# amp_summator_v_1_0.net
KiCad netlist of a schematic drawn in EAGLE
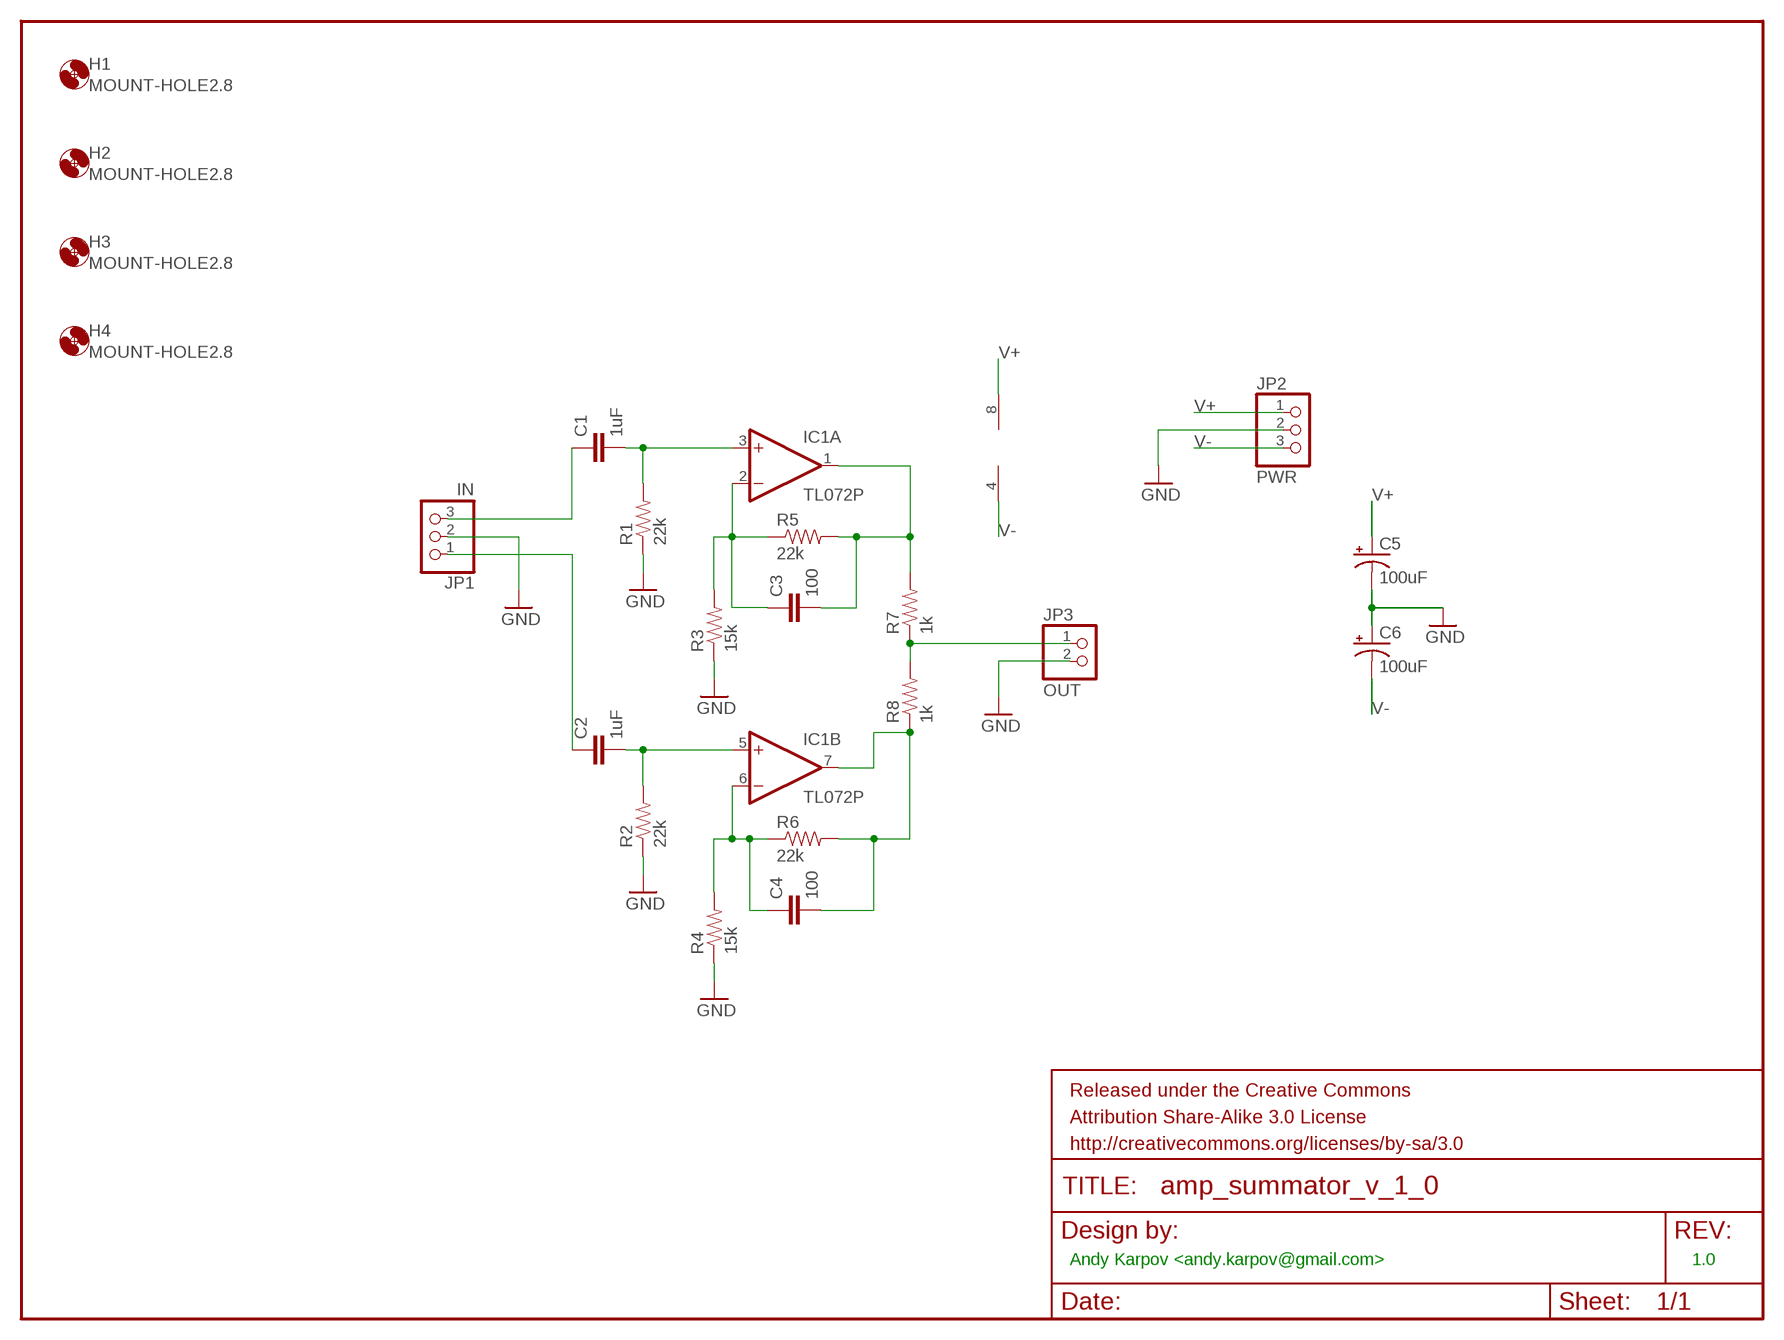
[diagram p0: schematic, sheet 1]

(export (version "E")
  (design (tool "Eeschema 10.0.6"))
  (components
    (comp (ref "C1")
      (value "1uF")
      (footprint "eagle-import:CAP-PTH-5MM")
      (libsource (lib "eagle-import") (part "CAPPTH1"))
    )
    (comp (ref "C2")
      (value "1uF")
      (footprint "eagle-import:CAP-PTH-5MM")
      (libsource (lib "eagle-import") (part "CAPPTH1"))
    )
    (comp (ref "C3")
      (value "100")
      (footprint "eagle-import:CAP-PTH-5MM")
      (libsource (lib "eagle-import") (part "CAPPTH1"))
    )
    (comp (ref "C4")
      (value "100")
      (footprint "eagle-import:CAP-PTH-5MM")
      (libsource (lib "eagle-import") (part "CAPPTH1"))
    )
    (comp (ref "C5")
      (value "100uF")
      (footprint "eagle-import:CPOL-RADIAL-100UF-25V")
      (libsource (lib "eagle-import") (part "CAP_POLPTH1"))
    )
    (comp (ref "C6")
      (value "100uF")
      (footprint "eagle-import:CPOL-RADIAL-100UF-25V")
      (libsource (lib "eagle-import") (part "CAP_POLPTH1"))
    )
    (comp (ref "FRAME1")
      (value "FRAME-LETTER")
      (footprint "eagle-import:CREATIVE_COMMONS")
      (libsource (lib "eagle-import") (part "FRAME-LETTER"))
    )
    (comp (ref "H1")
      (value "MOUNT-HOLE2.8")
      (footprint "eagle-import:2,8")
      (libsource (lib "eagle-import") (part "MOUNT-HOLE2.8"))
    )
    (comp (ref "H2")
      (value "MOUNT-HOLE2.8")
      (footprint "eagle-import:2,8")
      (libsource (lib "eagle-import") (part "MOUNT-HOLE2.8"))
    )
    (comp (ref "H3")
      (value "MOUNT-HOLE2.8")
      (footprint "eagle-import:2,8")
      (libsource (lib "eagle-import") (part "MOUNT-HOLE2.8"))
    )
    (comp (ref "H4")
      (value "MOUNT-HOLE2.8")
      (footprint "eagle-import:2,8")
      (libsource (lib "eagle-import") (part "MOUNT-HOLE2.8"))
    )
    (comp (ref "IC1")
      (value "TL072P")
      (footprint "eagle-import:DIL08")
      (libsource (lib "eagle-import") (part "TL072P"))
    )
    (comp (ref "JP1")
      (value "IN")
      (footprint "eagle-import:1X03")
      (libsource (lib "eagle-import") (part "PINHD-1X3"))
    )
    (comp (ref "JP2")
      (value "PWR")
      (footprint "eagle-import:1X03")
      (libsource (lib "eagle-import") (part "PINHD-1X3"))
    )
    (comp (ref "JP3")
      (value "OUT")
      (footprint "eagle-import:1X02")
      (libsource (lib "eagle-import") (part "PINHD-1X2"))
    )
    (comp (ref "R1")
      (value "22k")
      (footprint "eagle-import:AXIAL-0.4")
      (libsource (lib "eagle-import") (part "RESISTORPTH-1/4W"))
    )
    (comp (ref "R2")
      (value "22k")
      (footprint "eagle-import:AXIAL-0.4")
      (libsource (lib "eagle-import") (part "RESISTORPTH-1/4W"))
    )
    (comp (ref "R3")
      (value "15k")
      (footprint "eagle-import:AXIAL-0.4")
      (libsource (lib "eagle-import") (part "RESISTORPTH-1/4W"))
    )
    (comp (ref "R4")
      (value "15k")
      (footprint "eagle-import:AXIAL-0.4")
      (libsource (lib "eagle-import") (part "RESISTORPTH-1/4W"))
    )
    (comp (ref "R5")
      (value "22k")
      (footprint "eagle-import:AXIAL-0.4")
      (libsource (lib "eagle-import") (part "RESISTORPTH-1/4W"))
    )
    (comp (ref "R6")
      (value "22k")
      (footprint "eagle-import:AXIAL-0.4")
      (libsource (lib "eagle-import") (part "RESISTORPTH-1/4W"))
    )
    (comp (ref "R7")
      (value "1k")
      (footprint "eagle-import:AXIAL-0.4")
      (libsource (lib "eagle-import") (part "RESISTORPTH-1/4W"))
    )
    (comp (ref "R8")
      (value "1k")
      (footprint "eagle-import:AXIAL-0.4")
      (libsource (lib "eagle-import") (part "RESISTORPTH-1/4W"))
    )
  )
  (nets
    (net (code "1") (name "/V+") (class "Default")
      (node (ref "C5") (pin "1") (pinfunction "+_1") (pintype "passive"))
      (node (ref "IC1") (pin "8") (pinfunction "V+_8") (pintype "power_in"))
      (node (ref "JP2") (pin "1") (pinfunction "1_1") (pintype "passive"))
    )
    (net (code "2") (name "/V-") (class "Default")
      (node (ref "C6") (pin "2") (pinfunction "-_2") (pintype "passive"))
      (node (ref "IC1") (pin "4") (pinfunction "V-_4") (pintype "power_in"))
      (node (ref "JP2") (pin "3") (pinfunction "3_3") (pintype "passive"))
    )
    (net (code "3") (name "GND") (class "Default")
      (node (ref "C5") (pin "2") (pinfunction "-_2") (pintype "passive"))
      (node (ref "C6") (pin "1") (pinfunction "+_1") (pintype "passive"))
      (node (ref "JP1") (pin "2") (pinfunction "2_2") (pintype "passive"))
      (node (ref "JP2") (pin "2") (pinfunction "2_2") (pintype "passive"))
      (node (ref "JP3") (pin "2") (pinfunction "2_2") (pintype "passive"))
      (node (ref "R1") (pin "P$1") (pinfunction "1_P$1") (pintype "passive"))
      (node (ref "R2") (pin "P$1") (pinfunction "1_P$1") (pintype "passive"))
      (node (ref "R3") (pin "P$1") (pinfunction "1_P$1") (pintype "passive"))
      (node (ref "R4") (pin "P$1") (pinfunction "1_P$1") (pintype "passive"))
    )
    (net (code "4") (name "Net-(C1-Pad1)") (class "Default")
      (node (ref "C1") (pin "1") (pinfunction "1_1") (pintype "passive"))
      (node (ref "JP1") (pin "3") (pinfunction "3_3") (pintype "passive"))
    )
    (net (code "5") (name "Net-(C2-Pad1)") (class "Default")
      (node (ref "C2") (pin "1") (pinfunction "1_1") (pintype "passive"))
      (node (ref "JP1") (pin "1") (pinfunction "1_1") (pintype "passive"))
    )
    (net (code "6") (name "Net-(IC1A-+IN)") (class "Default")
      (node (ref "C1") (pin "2") (pinfunction "2_2") (pintype "passive"))
      (node (ref "IC1") (pin "3") (pinfunction "+IN_3") (pintype "input"))
      (node (ref "R1") (pin "P$2") (pinfunction "2_P$2") (pintype "passive"))
    )
    (net (code "7") (name "Net-(IC1A--IN)") (class "Default")
      (node (ref "C3") (pin "1") (pinfunction "1_1") (pintype "passive"))
      (node (ref "IC1") (pin "2") (pinfunction "-IN_2") (pintype "input"))
      (node (ref "R3") (pin "P$2") (pinfunction "2_P$2") (pintype "passive"))
      (node (ref "R5") (pin "P$1") (pinfunction "1_P$1") (pintype "passive"))
    )
    (net (code "8") (name "Net-(IC1A-OUT)") (class "Default")
      (node (ref "C3") (pin "2") (pinfunction "2_2") (pintype "passive"))
      (node (ref "IC1") (pin "1") (pinfunction "OUT_1") (pintype "output"))
      (node (ref "R5") (pin "P$2") (pinfunction "2_P$2") (pintype "passive"))
      (node (ref "R7") (pin "P$2") (pinfunction "2_P$2") (pintype "passive"))
    )
    (net (code "9") (name "Net-(IC1B-+IN)") (class "Default")
      (node (ref "C2") (pin "2") (pinfunction "2_2") (pintype "passive"))
      (node (ref "IC1") (pin "5") (pinfunction "+IN_5") (pintype "input"))
      (node (ref "R2") (pin "P$2") (pinfunction "2_P$2") (pintype "passive"))
    )
    (net (code "10") (name "Net-(IC1B--IN)") (class "Default")
      (node (ref "C4") (pin "1") (pinfunction "1_1") (pintype "passive"))
      (node (ref "IC1") (pin "6") (pinfunction "-IN_6") (pintype "input"))
      (node (ref "R4") (pin "P$2") (pinfunction "2_P$2") (pintype "passive"))
      (node (ref "R6") (pin "P$1") (pinfunction "1_P$1") (pintype "passive"))
    )
    (net (code "11") (name "Net-(IC1B-OUT)") (class "Default")
      (node (ref "C4") (pin "2") (pinfunction "2_2") (pintype "passive"))
      (node (ref "IC1") (pin "7") (pinfunction "OUT_7") (pintype "output"))
      (node (ref "R6") (pin "P$2") (pinfunction "2_P$2") (pintype "passive"))
      (node (ref "R8") (pin "P$1") (pinfunction "1_P$1") (pintype "passive"))
    )
    (net (code "12") (name "Net-(R7-1)") (class "Default")
      (node (ref "JP3") (pin "1") (pinfunction "1_1") (pintype "passive"))
      (node (ref "R7") (pin "P$1") (pinfunction "1_P$1") (pintype "passive"))
      (node (ref "R8") (pin "P$2") (pinfunction "2_P$2") (pintype "passive"))
    )
  )
)
